# main.net
KiCad netlist of a schematic drawn in EAGLE
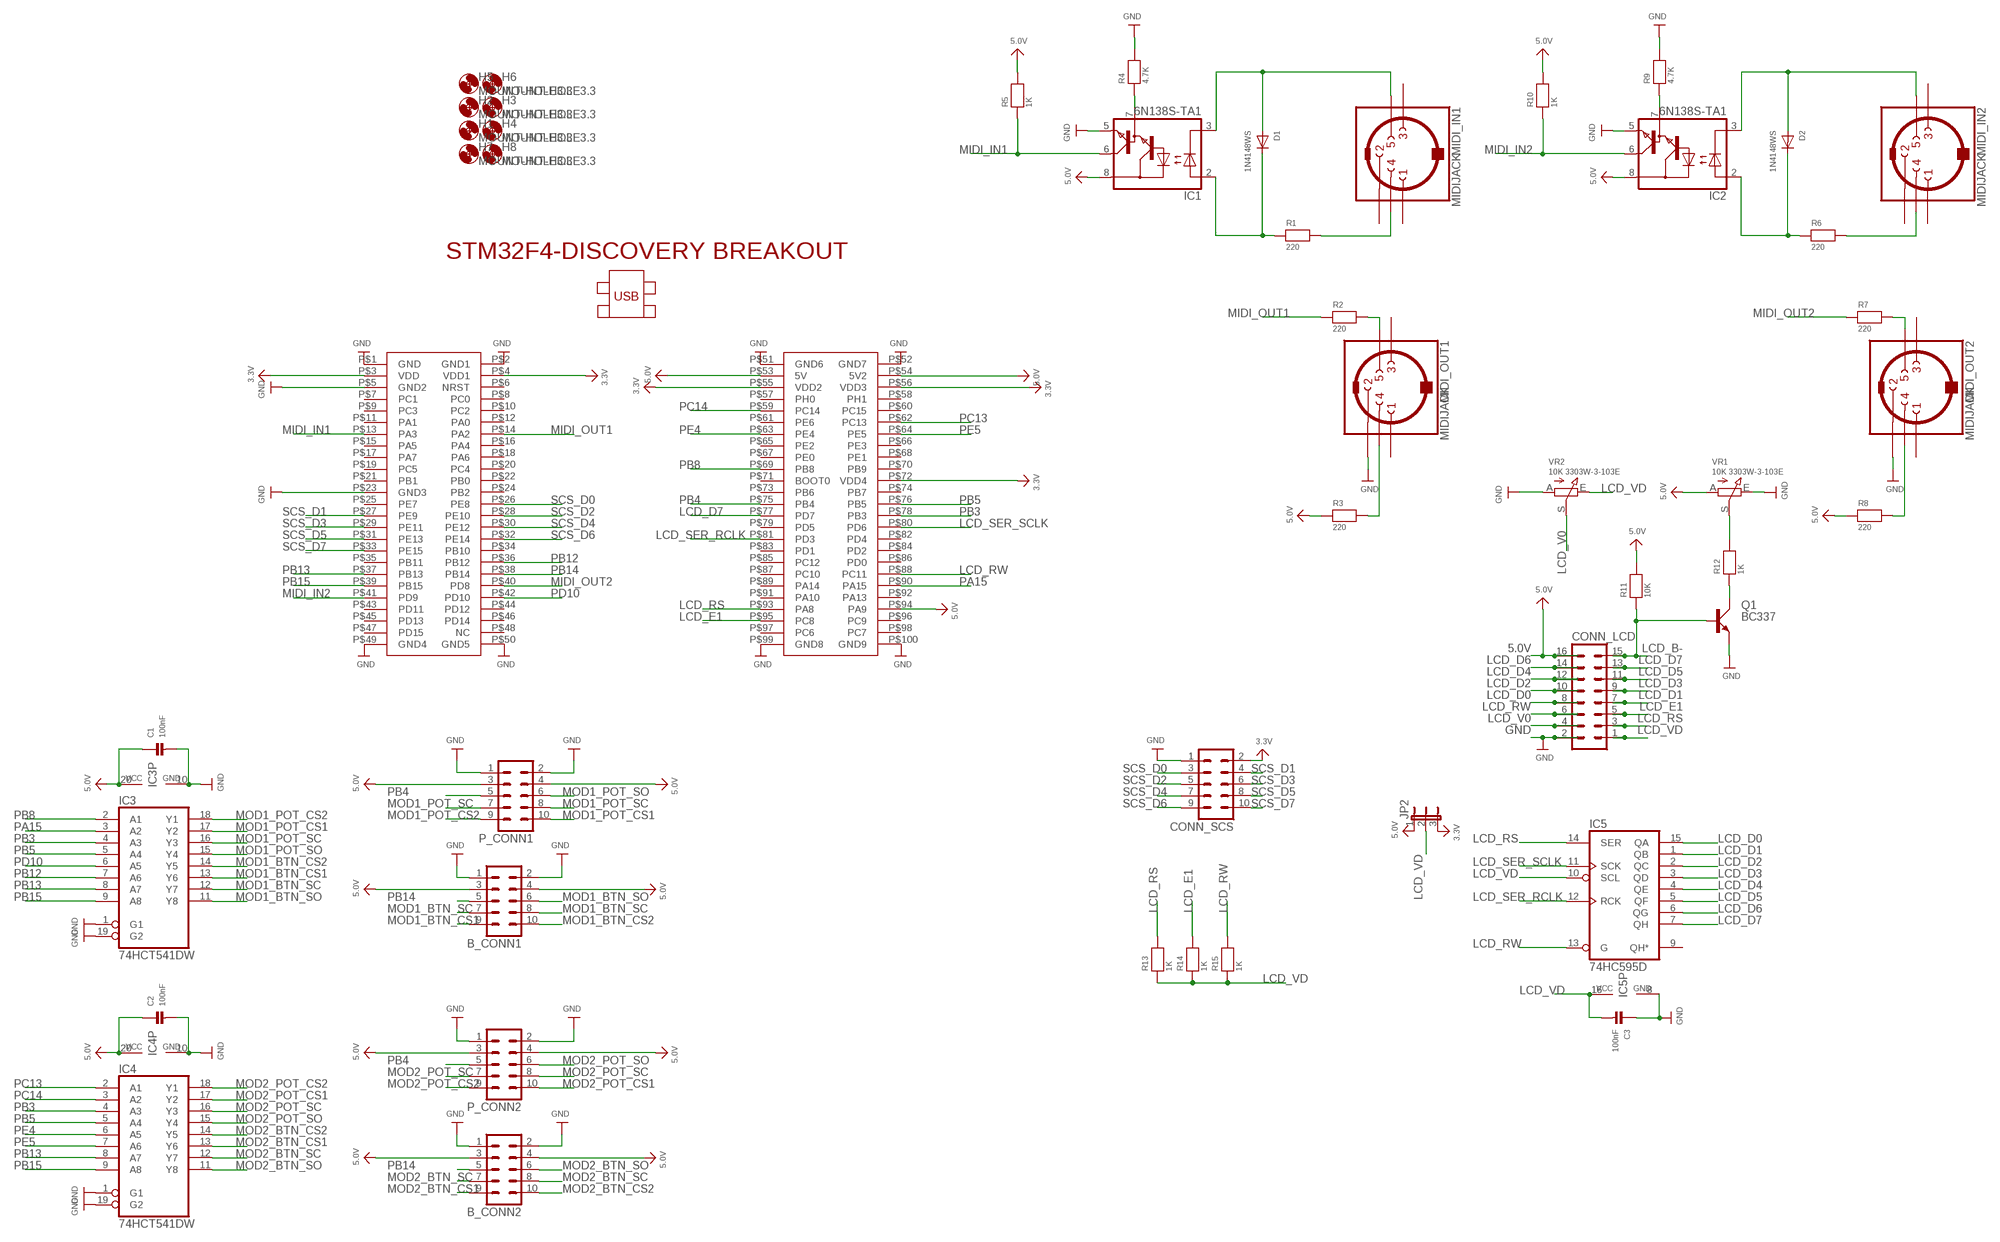
[diagram p0: schematic, sheet 1]

(export (version "E")
  (design (tool "Eeschema 10.0.6"))
  (components
    (comp (ref "B_CONN1")
      (value "ML10")
      (footprint "eagle-import:ML10")
      (libsource (lib "eagle-import") (part "ML10"))
    )
    (comp (ref "B_CONN2")
      (value "ML10")
      (footprint "eagle-import:ML10")
      (libsource (lib "eagle-import") (part "ML10"))
    )
    (comp (ref "C1")
      (value "100nF")
      (footprint "eagle-import:0603")
      (libsource (lib "eagle-import") (part "CAP_CERAMIC0603"))
    )
    (comp (ref "C2")
      (value "100nF")
      (footprint "eagle-import:0603")
      (libsource (lib "eagle-import") (part "CAP_CERAMIC0603"))
    )
    (comp (ref "C3")
      (value "100nF")
      (footprint "eagle-import:0603")
      (libsource (lib "eagle-import") (part "CAP_CERAMIC0603"))
    )
    (comp (ref "CONN_LCD")
      (value "ML16")
      (footprint "eagle-import:ML16")
      (libsource (lib "eagle-import") (part "ML16"))
    )
    (comp (ref "CONN_SCS")
      (value "ML10")
      (footprint "eagle-import:ML10")
      (libsource (lib "eagle-import") (part "ML10"))
    )
    (comp (ref "D1")
      (value "1N4148WS")
      (footprint "eagle-import:SOD-323")
      (libsource (lib "eagle-import") (part "DIODESOD-323"))
    )
    (comp (ref "D2")
      (value "1N4148WS")
      (footprint "eagle-import:SOD-323")
      (libsource (lib "eagle-import") (part "DIODESOD-323"))
    )
    (comp (ref "H1")
      (value "MOUNT-HOLE3.3")
      (footprint "eagle-import:3,3")
      (libsource (lib "eagle-import") (part "MOUNT-HOLE3.3"))
    )
    (comp (ref "H2")
      (value "MOUNT-HOLE3.3")
      (footprint "eagle-import:3,3")
      (libsource (lib "eagle-import") (part "MOUNT-HOLE3.3"))
    )
    (comp (ref "H3")
      (value "MOUNT-HOLE3.3")
      (footprint "eagle-import:3,3")
      (libsource (lib "eagle-import") (part "MOUNT-HOLE3.3"))
    )
    (comp (ref "H4")
      (value "MOUNT-HOLE3.3")
      (footprint "eagle-import:3,3")
      (libsource (lib "eagle-import") (part "MOUNT-HOLE3.3"))
    )
    (comp (ref "H5")
      (value "MOUNT-HOLE3.3")
      (footprint "eagle-import:3,3")
      (libsource (lib "eagle-import") (part "MOUNT-HOLE3.3"))
    )
    (comp (ref "H6")
      (value "MOUNT-HOLE3.3")
      (footprint "eagle-import:3,3")
      (libsource (lib "eagle-import") (part "MOUNT-HOLE3.3"))
    )
    (comp (ref "H7")
      (value "MOUNT-HOLE3.3")
      (footprint "eagle-import:3,3")
      (libsource (lib "eagle-import") (part "MOUNT-HOLE3.3"))
    )
    (comp (ref "H8")
      (value "MOUNT-HOLE3.3")
      (footprint "eagle-import:3,3")
      (libsource (lib "eagle-import") (part "MOUNT-HOLE3.3"))
    )
    (comp (ref "IC1")
      (value "6N138S-TA1")
      (footprint "eagle-import:SO8-GW300")
      (libsource (lib "eagle-import") (part "6N138SMD"))
    )
    (comp (ref "IC2")
      (value "6N138S-TA1")
      (footprint "eagle-import:SO8-GW300")
      (libsource (lib "eagle-import") (part "6N138SMD"))
    )
    (comp (ref "IC3")
      (value "74HCT541DW")
      (footprint "eagle-import:SO20W")
      (libsource (lib "eagle-import") (part "74541DWHCT"))
    )
    (comp (ref "IC4")
      (value "74HCT541DW")
      (footprint "eagle-import:SO20W")
      (libsource (lib "eagle-import") (part "74541DWHCT"))
    )
    (comp (ref "IC5")
      (value "74HC595D")
      (footprint "eagle-import:SO16")
      (libsource (lib "eagle-import") (part "74595DHC"))
    )
    (comp (ref "JP2")
      (value "JUMPER3")
      (footprint "eagle-import:JUMPER3")
      (libsource (lib "eagle-import") (part "JUMPER3"))
    )
    (comp (ref "MIDI_IN1")
      (value "MIDIJACK")
      (footprint "eagle-import:CP-2350")
      (libsource (lib "eagle-import") (part "MIDIJACK"))
    )
    (comp (ref "MIDI_IN2")
      (value "MIDIJACK")
      (footprint "eagle-import:CP-2350")
      (libsource (lib "eagle-import") (part "MIDIJACK"))
    )
    (comp (ref "MIDI_OUT1")
      (value "MIDIJACK")
      (footprint "eagle-import:CP-2350")
      (libsource (lib "eagle-import") (part "MIDIJACK"))
    )
    (comp (ref "MIDI_OUT2")
      (value "MIDIJACK")
      (footprint "eagle-import:CP-2350")
      (libsource (lib "eagle-import") (part "MIDIJACK"))
    )
    (comp (ref "P_CONN1")
      (value "ML10")
      (footprint "eagle-import:ML10")
      (libsource (lib "eagle-import") (part "ML10"))
    )
    (comp (ref "P_CONN2")
      (value "ML10")
      (footprint "eagle-import:ML10")
      (libsource (lib "eagle-import") (part "ML10"))
    )
    (comp (ref "Q1")
      (value "BC337")
      (footprint "eagle-import:SOT54A")
      (libsource (lib "eagle-import") (part "BC337"))
    )
    (comp (ref "R1")
      (value "220")
      (footprint "eagle-import:_0603")
      (libsource (lib "eagle-import") (part "RESISTOR_0603"))
    )
    (comp (ref "R2")
      (value "220")
      (footprint "eagle-import:_0603")
      (libsource (lib "eagle-import") (part "RESISTOR_0603"))
    )
    (comp (ref "R3")
      (value "220")
      (footprint "eagle-import:_0603")
      (libsource (lib "eagle-import") (part "RESISTOR_0603"))
    )
    (comp (ref "R4")
      (value "4.7K")
      (footprint "eagle-import:_0603")
      (libsource (lib "eagle-import") (part "RESISTOR_0603"))
    )
    (comp (ref "R5")
      (value "1K")
      (footprint "eagle-import:_0603")
      (libsource (lib "eagle-import") (part "RESISTOR_0603"))
    )
    (comp (ref "R6")
      (value "220")
      (footprint "eagle-import:_0603")
      (libsource (lib "eagle-import") (part "RESISTOR_0603"))
    )
    (comp (ref "R7")
      (value "220")
      (footprint "eagle-import:_0603")
      (libsource (lib "eagle-import") (part "RESISTOR_0603"))
    )
    (comp (ref "R8")
      (value "220")
      (footprint "eagle-import:_0603")
      (libsource (lib "eagle-import") (part "RESISTOR_0603"))
    )
    (comp (ref "R9")
      (value "4.7K")
      (footprint "eagle-import:_0603")
      (libsource (lib "eagle-import") (part "RESISTOR_0603"))
    )
    (comp (ref "R10")
      (value "1K")
      (footprint "eagle-import:_0603")
      (libsource (lib "eagle-import") (part "RESISTOR_0603"))
    )
    (comp (ref "R11")
      (value "10K")
      (footprint "eagle-import:_0603")
      (libsource (lib "eagle-import") (part "RESISTOR_0603"))
    )
    (comp (ref "R12")
      (value "1K")
      (footprint "eagle-import:_0603")
      (libsource (lib "eagle-import") (part "RESISTOR_0603"))
    )
    (comp (ref "R13")
      (value "1K")
      (footprint "eagle-import:_0603")
      (libsource (lib "eagle-import") (part "RESISTOR_0603"))
    )
    (comp (ref "R14")
      (value "1K")
      (footprint "eagle-import:_0603")
      (libsource (lib "eagle-import") (part "RESISTOR_0603"))
    )
    (comp (ref "R15")
      (value "1K")
      (footprint "eagle-import:_0603")
      (libsource (lib "eagle-import") (part "RESISTOR_0603"))
    )
    (comp (ref "U$1")
      (value "STM32F4-DISCOVERY")
      (footprint "eagle-import:STM32F4-DISCOVERY")
      (libsource (lib "eagle-import") (part "STM32F4-DISCOVERY"))
    )
    (comp (ref "VR1")
      (value "10K 3303W-3-103E")
      (footprint "eagle-import:TRIMPOT_BOURNS3MM")
      (libsource (lib "eagle-import") (part "TRIMPOT10K_BOURNS"))
    )
    (comp (ref "VR2")
      (value "10K 3303W-3-103E")
      (footprint "eagle-import:TRIMPOT_BOURNS3MM")
      (libsource (lib "eagle-import") (part "TRIMPOT10K_BOURNS"))
    )
  )
  (nets
    (net (code "1") (name "/LCD_B-") (class "Default")
      (node (ref "CONN_LCD") (pin "15") (pinfunction "15_15") (pintype "passive"))
      (node (ref "Q1") (pin "B") (pinfunction "B_B") (pintype "passive"))
      (node (ref "R11") (pin "1") (pinfunction "1_1") (pintype "passive"))
    )
    (net (code "2") (name "/LCD_D0") (class "Default")
      (node (ref "CONN_LCD") (pin "8") (pinfunction "8_8") (pintype "passive"))
      (node (ref "IC5") (pin "15") (pinfunction "QA_15") (pintype "tri_state"))
    )
    (net (code "3") (name "/LCD_D1") (class "Default")
      (node (ref "CONN_LCD") (pin "7") (pinfunction "7_7") (pintype "passive"))
      (node (ref "IC5") (pin "1") (pinfunction "QB_1") (pintype "tri_state"))
    )
    (net (code "4") (name "/LCD_D2") (class "Default")
      (node (ref "CONN_LCD") (pin "10") (pinfunction "10_10") (pintype "passive"))
      (node (ref "IC5") (pin "2") (pinfunction "QC_2") (pintype "tri_state"))
    )
    (net (code "5") (name "/LCD_D3") (class "Default")
      (node (ref "CONN_LCD") (pin "9") (pinfunction "9_9") (pintype "passive"))
      (node (ref "IC5") (pin "3") (pinfunction "QD_3") (pintype "tri_state"))
    )
    (net (code "6") (name "/LCD_D4") (class "Default")
      (node (ref "CONN_LCD") (pin "12") (pinfunction "12_12") (pintype "passive"))
      (node (ref "IC5") (pin "4") (pinfunction "QE_4") (pintype "tri_state"))
    )
    (net (code "7") (name "/LCD_D5") (class "Default")
      (node (ref "CONN_LCD") (pin "11") (pinfunction "11_11") (pintype "passive"))
      (node (ref "IC5") (pin "5") (pinfunction "QF_5") (pintype "tri_state"))
    )
    (net (code "8") (name "/LCD_D6") (class "Default")
      (node (ref "CONN_LCD") (pin "14") (pinfunction "14_14") (pintype "passive"))
      (node (ref "IC5") (pin "6") (pinfunction "QG_6") (pintype "tri_state"))
    )
    (net (code "9") (name "/LCD_D7") (class "Default")
      (node (ref "CONN_LCD") (pin "13") (pinfunction "13_13") (pintype "passive"))
      (node (ref "IC5") (pin "7") (pinfunction "QH_7") (pintype "tri_state"))
      (node (ref "U$1") (pin "P$77") (pinfunction "PD7_P$77") (pintype "bidirectional"))
    )
    (net (code "10") (name "/LCD_E1") (class "Default")
      (node (ref "CONN_LCD") (pin "5") (pinfunction "5_5") (pintype "passive"))
      (node (ref "R14") (pin "2") (pinfunction "2_2") (pintype "passive"))
      (node (ref "U$1") (pin "P$95") (pinfunction "PC8_P$95") (pintype "bidirectional"))
    )
    (net (code "11") (name "/LCD_RS") (class "Default")
      (node (ref "CONN_LCD") (pin "3") (pinfunction "3_3") (pintype "passive"))
      (node (ref "IC5") (pin "14") (pinfunction "SER_14") (pintype "input"))
      (node (ref "R13") (pin "2") (pinfunction "2_2") (pintype "passive"))
      (node (ref "U$1") (pin "P$93") (pinfunction "PA8_P$93") (pintype "bidirectional"))
    )
    (net (code "12") (name "/LCD_RW") (class "Default")
      (node (ref "CONN_LCD") (pin "6") (pinfunction "6_6") (pintype "passive"))
      (node (ref "IC5") (pin "13") (pinfunction "G_13") (pintype "input"))
      (node (ref "R15") (pin "2") (pinfunction "2_2") (pintype "passive"))
      (node (ref "U$1") (pin "P$88") (pinfunction "PC11_P$88") (pintype "bidirectional"))
    )
    (net (code "13") (name "/LCD_SER_RCLK") (class "Default")
      (node (ref "IC5") (pin "12") (pinfunction "RCK_12") (pintype "input"))
      (node (ref "U$1") (pin "P$81") (pinfunction "PD3_P$81") (pintype "bidirectional"))
    )
    (net (code "14") (name "/LCD_SER_SCLK") (class "Default")
      (node (ref "IC5") (pin "11") (pinfunction "SCK_11") (pintype "input"))
      (node (ref "U$1") (pin "P$80") (pinfunction "PD6_P$80") (pintype "bidirectional"))
    )
    (net (code "15") (name "/LCD_V0") (class "Default")
      (node (ref "CONN_LCD") (pin "4") (pinfunction "4_4") (pintype "passive"))
      (node (ref "VR2") (pin "S") (pinfunction "S_S") (pintype "passive"))
    )
    (net (code "16") (name "/LCD_VD") (class "Default")
      (node (ref "C3") (pin "2") (pinfunction "P$2_2") (pintype "passive"))
      (node (ref "CONN_LCD") (pin "1") (pinfunction "1_1") (pintype "passive"))
      (node (ref "IC5") (pin "10") (pinfunction "SCL_10") (pintype "input"))
      (node (ref "IC5") (pin "16") (pinfunction "VCC_16") (pintype "power_in"))
      (node (ref "JP2") (pin "2") (pinfunction "2_2") (pintype "passive"))
      (node (ref "R13") (pin "1") (pinfunction "1_1") (pintype "passive"))
      (node (ref "R14") (pin "1") (pinfunction "1_1") (pintype "passive"))
      (node (ref "R15") (pin "1") (pinfunction "1_1") (pintype "passive"))
      (node (ref "VR2") (pin "E") (pinfunction "E_E") (pintype "passive"))
    )
    (net (code "17") (name "/MIDI_IN1") (class "Default")
      (node (ref "IC1") (pin "6") (pinfunction "VO_6") (pintype "passive"))
      (node (ref "R5") (pin "1") (pinfunction "1_1") (pintype "passive"))
      (node (ref "U$1") (pin "P$13") (pinfunction "PA3_P$13") (pintype "bidirectional"))
    )
    (net (code "18") (name "/MIDI_IN2") (class "Default")
      (node (ref "IC2") (pin "6") (pinfunction "VO_6") (pintype "passive"))
      (node (ref "R10") (pin "1") (pinfunction "1_1") (pintype "passive"))
      (node (ref "U$1") (pin "P$41") (pinfunction "PD9_P$41") (pintype "bidirectional"))
    )
    (net (code "19") (name "/MIDI_OUT1") (class "Default")
      (node (ref "R2") (pin "1") (pinfunction "1_1") (pintype "passive"))
      (node (ref "U$1") (pin "P$14") (pinfunction "PA2_P$14") (pintype "bidirectional"))
    )
    (net (code "20") (name "/MIDI_OUT2") (class "Default")
      (node (ref "R7") (pin "1") (pinfunction "1_1") (pintype "passive"))
      (node (ref "U$1") (pin "P$40") (pinfunction "PD8_P$40") (pintype "bidirectional"))
    )
    (net (code "21") (name "/MOD1_BTN_CS1") (class "Default")
      (node (ref "B_CONN1") (pin "9") (pinfunction "9_9") (pintype "passive"))
      (node (ref "IC3") (pin "13") (pinfunction "Y6_13") (pintype "tri_state"))
    )
    (net (code "22") (name "/MOD1_BTN_CS2") (class "Default")
      (node (ref "B_CONN1") (pin "10") (pinfunction "10_10") (pintype "passive"))
      (node (ref "IC3") (pin "14") (pinfunction "Y5_14") (pintype "tri_state"))
    )
    (net (code "23") (name "/MOD1_BTN_SC") (class "Default")
      (node (ref "B_CONN1") (pin "7") (pinfunction "7_7") (pintype "passive"))
      (node (ref "B_CONN1") (pin "8") (pinfunction "8_8") (pintype "passive"))
      (node (ref "IC3") (pin "12") (pinfunction "Y7_12") (pintype "tri_state"))
    )
    (net (code "24") (name "/MOD1_BTN_SO") (class "Default")
      (node (ref "B_CONN1") (pin "6") (pinfunction "6_6") (pintype "passive"))
      (node (ref "IC3") (pin "11") (pinfunction "Y8_11") (pintype "tri_state"))
    )
    (net (code "25") (name "/MOD1_POT_CS1") (class "Default")
      (node (ref "IC3") (pin "17") (pinfunction "Y2_17") (pintype "tri_state"))
      (node (ref "P_CONN1") (pin "10") (pinfunction "10_10") (pintype "passive"))
    )
    (net (code "26") (name "/MOD1_POT_CS2") (class "Default")
      (node (ref "IC3") (pin "18") (pinfunction "Y1_18") (pintype "tri_state"))
      (node (ref "P_CONN1") (pin "9") (pinfunction "9_9") (pintype "passive"))
    )
    (net (code "27") (name "/MOD1_POT_SC") (class "Default")
      (node (ref "IC3") (pin "16") (pinfunction "Y3_16") (pintype "tri_state"))
      (node (ref "P_CONN1") (pin "7") (pinfunction "7_7") (pintype "passive"))
      (node (ref "P_CONN1") (pin "8") (pinfunction "8_8") (pintype "passive"))
    )
    (net (code "28") (name "/MOD1_POT_SO") (class "Default")
      (node (ref "IC3") (pin "15") (pinfunction "Y4_15") (pintype "tri_state"))
      (node (ref "P_CONN1") (pin "6") (pinfunction "6_6") (pintype "passive"))
    )
    (net (code "29") (name "/MOD2_BTN_CS1") (class "Default")
      (node (ref "B_CONN2") (pin "9") (pinfunction "9_9") (pintype "passive"))
      (node (ref "IC4") (pin "13") (pinfunction "Y6_13") (pintype "tri_state"))
    )
    (net (code "30") (name "/MOD2_BTN_CS2") (class "Default")
      (node (ref "B_CONN2") (pin "10") (pinfunction "10_10") (pintype "passive"))
      (node (ref "IC4") (pin "14") (pinfunction "Y5_14") (pintype "tri_state"))
    )
    (net (code "31") (name "/MOD2_BTN_SC") (class "Default")
      (node (ref "B_CONN2") (pin "7") (pinfunction "7_7") (pintype "passive"))
      (node (ref "B_CONN2") (pin "8") (pinfunction "8_8") (pintype "passive"))
      (node (ref "IC4") (pin "12") (pinfunction "Y7_12") (pintype "tri_state"))
    )
    (net (code "32") (name "/MOD2_BTN_SO") (class "Default")
      (node (ref "B_CONN2") (pin "6") (pinfunction "6_6") (pintype "passive"))
      (node (ref "IC4") (pin "11") (pinfunction "Y8_11") (pintype "tri_state"))
    )
    (net (code "33") (name "/MOD2_POT_CS1") (class "Default")
      (node (ref "IC4") (pin "17") (pinfunction "Y2_17") (pintype "tri_state"))
      (node (ref "P_CONN2") (pin "10") (pinfunction "10_10") (pintype "passive"))
    )
    (net (code "34") (name "/MOD2_POT_CS2") (class "Default")
      (node (ref "IC4") (pin "18") (pinfunction "Y1_18") (pintype "tri_state"))
      (node (ref "P_CONN2") (pin "9") (pinfunction "9_9") (pintype "passive"))
    )
    (net (code "35") (name "/MOD2_POT_SC") (class "Default")
      (node (ref "IC4") (pin "16") (pinfunction "Y3_16") (pintype "tri_state"))
      (node (ref "P_CONN2") (pin "7") (pinfunction "7_7") (pintype "passive"))
      (node (ref "P_CONN2") (pin "8") (pinfunction "8_8") (pintype "passive"))
    )
    (net (code "36") (name "/MOD2_POT_SO") (class "Default")
      (node (ref "IC4") (pin "15") (pinfunction "Y4_15") (pintype "tri_state"))
      (node (ref "P_CONN2") (pin "6") (pinfunction "6_6") (pintype "passive"))
    )
    (net (code "37") (name "/PA15") (class "Default")
      (node (ref "IC3") (pin "3") (pinfunction "A2_3") (pintype "input"))
      (node (ref "U$1") (pin "P$90") (pinfunction "PA15_P$90") (pintype "bidirectional"))
    )
    (net (code "38") (name "/PB3") (class "Default")
      (node (ref "IC3") (pin "4") (pinfunction "A3_4") (pintype "input"))
      (node (ref "IC4") (pin "4") (pinfunction "A3_4") (pintype "input"))
      (node (ref "U$1") (pin "P$78") (pinfunction "PB3_P$78") (pintype "bidirectional"))
    )
    (net (code "39") (name "/PB4") (class "Default")
      (node (ref "P_CONN1") (pin "5") (pinfunction "5_5") (pintype "passive"))
      (node (ref "P_CONN2") (pin "5") (pinfunction "5_5") (pintype "passive"))
      (node (ref "U$1") (pin "P$75") (pinfunction "PB4_P$75") (pintype "bidirectional"))
    )
    (net (code "40") (name "/PB5") (class "Default")
      (node (ref "IC3") (pin "5") (pinfunction "A4_5") (pintype "input"))
      (node (ref "IC4") (pin "5") (pinfunction "A4_5") (pintype "input"))
      (node (ref "U$1") (pin "P$76") (pinfunction "PB5_P$76") (pintype "bidirectional"))
    )
    (net (code "41") (name "/PB8") (class "Default")
      (node (ref "IC3") (pin "2") (pinfunction "A1_2") (pintype "input"))
      (node (ref "U$1") (pin "P$69") (pinfunction "PB8_P$69") (pintype "bidirectional"))
    )
    (net (code "42") (name "/PB12") (class "Default")
      (node (ref "IC3") (pin "7") (pinfunction "A6_7") (pintype "input"))
      (node (ref "U$1") (pin "P$36") (pinfunction "PB12_P$36") (pintype "bidirectional"))
    )
    (net (code "43") (name "/PB13") (class "Default")
      (node (ref "IC3") (pin "8") (pinfunction "A7_8") (pintype "input"))
      (node (ref "IC4") (pin "8") (pinfunction "A7_8") (pintype "input"))
      (node (ref "U$1") (pin "P$37") (pinfunction "PB13_P$37") (pintype "bidirectional"))
    )
    (net (code "44") (name "/PB14") (class "Default")
      (node (ref "B_CONN1") (pin "5") (pinfunction "5_5") (pintype "passive"))
      (node (ref "B_CONN2") (pin "5") (pinfunction "5_5") (pintype "passive"))
      (node (ref "U$1") (pin "P$38") (pinfunction "PB14_P$38") (pintype "bidirectional"))
    )
    (net (code "45") (name "/PB15") (class "Default")
      (node (ref "IC3") (pin "9") (pinfunction "A8_9") (pintype "input"))
      (node (ref "IC4") (pin "9") (pinfunction "A8_9") (pintype "input"))
      (node (ref "U$1") (pin "P$39") (pinfunction "PB15_P$39") (pintype "bidirectional"))
    )
    (net (code "46") (name "/PC13") (class "Default")
      (node (ref "IC4") (pin "2") (pinfunction "A1_2") (pintype "input"))
      (node (ref "U$1") (pin "P$62") (pinfunction "PC13_P$62") (pintype "bidirectional"))
    )
    (net (code "47") (name "/PC14") (class "Default")
      (node (ref "IC4") (pin "3") (pinfunction "A2_3") (pintype "input"))
      (node (ref "U$1") (pin "P$59") (pinfunction "PC14_P$59") (pintype "bidirectional"))
    )
    (net (code "48") (name "/PD10") (class "Default")
      (node (ref "IC3") (pin "6") (pinfunction "A5_6") (pintype "input"))
      (node (ref "U$1") (pin "P$42") (pinfunction "PD10_P$42") (pintype "bidirectional"))
    )
    (net (code "49") (name "/PE4") (class "Default")
      (node (ref "IC4") (pin "6") (pinfunction "A5_6") (pintype "input"))
      (node (ref "U$1") (pin "P$63") (pinfunction "PE4_P$63") (pintype "bidirectional"))
    )
    (net (code "50") (name "/PE5") (class "Default")
      (node (ref "IC4") (pin "7") (pinfunction "A6_7") (pintype "input"))
      (node (ref "U$1") (pin "P$64") (pinfunction "PE5_P$64") (pintype "bidirectional"))
    )
    (net (code "51") (name "/SCS_D0") (class "Default")
      (node (ref "CONN_SCS") (pin "3") (pinfunction "3_3") (pintype "passive"))
      (node (ref "U$1") (pin "P$26") (pinfunction "PE8_P$26") (pintype "bidirectional"))
    )
    (net (code "52") (name "/SCS_D1") (class "Default")
      (node (ref "CONN_SCS") (pin "4") (pinfunction "4_4") (pintype "passive"))
      (node (ref "U$1") (pin "P$27") (pinfunction "PE9_P$27") (pintype "bidirectional"))
    )
    (net (code "53") (name "/SCS_D2") (class "Default")
      (node (ref "CONN_SCS") (pin "5") (pinfunction "5_5") (pintype "passive"))
      (node (ref "U$1") (pin "P$28") (pinfunction "PE10_P$28") (pintype "bidirectional"))
    )
    (net (code "54") (name "/SCS_D3") (class "Default")
      (node (ref "CONN_SCS") (pin "6") (pinfunction "6_6") (pintype "passive"))
      (node (ref "U$1") (pin "P$29") (pinfunction "PE11_P$29") (pintype "bidirectional"))
    )
    (net (code "55") (name "/SCS_D4") (class "Default")
      (node (ref "CONN_SCS") (pin "7") (pinfunction "7_7") (pintype "passive"))
      (node (ref "U$1") (pin "P$30") (pinfunction "PE12_P$30") (pintype "bidirectional"))
    )
    (net (code "56") (name "/SCS_D5") (class "Default")
      (node (ref "CONN_SCS") (pin "8") (pinfunction "8_8") (pintype "passive"))
      (node (ref "U$1") (pin "P$31") (pinfunction "PE13_P$31") (pintype "bidirectional"))
    )
    (net (code "57") (name "/SCS_D6") (class "Default")
      (node (ref "CONN_SCS") (pin "9") (pinfunction "9_9") (pintype "passive"))
      (node (ref "U$1") (pin "P$32") (pinfunction "PE14_P$32") (pintype "bidirectional"))
    )
    (net (code "58") (name "/SCS_D7") (class "Default")
      (node (ref "CONN_SCS") (pin "10") (pinfunction "10_10") (pintype "passive"))
      (node (ref "U$1") (pin "P$33") (pinfunction "PE15_P$33") (pintype "bidirectional"))
    )
    (net (code "59") (name "3.3V") (class "Default")
      (node (ref "CONN_SCS") (pin "2") (pinfunction "2_2") (pintype "passive"))
      (node (ref "JP2") (pin "3") (pinfunction "3_3") (pintype "passive"))
      (node (ref "U$1") (pin "P$3") (pinfunction "VDD_P$3") (pintype "bidirectional"))
      (node (ref "U$1") (pin "P$4") (pinfunction "VDD1_P$4") (pintype "bidirectional"))
      (node (ref "U$1") (pin "P$55") (pinfunction "VDD2_P$55") (pintype "bidirectional"))
      (node (ref "U$1") (pin "P$56") (pinfunction "VDD3_P$56") (pintype "bidirectional"))
      (node (ref "U$1") (pin "P$72") (pinfunction "VDD4_P$72") (pintype "bidirectional"))
    )
    (net (code "60") (name "5.0V") (class "Default")
      (node (ref "B_CONN1") (pin "3") (pinfunction "3_3") (pintype "passive"))
      (node (ref "B_CONN1") (pin "4") (pinfunction "4_4") (pintype "passive"))
      (node (ref "B_CONN2") (pin "3") (pinfunction "3_3") (pintype "passive"))
      (node (ref "B_CONN2") (pin "4") (pinfunction "4_4") (pintype "passive"))
      (node (ref "C1") (pin "1") (pinfunction "P$1_1") (pintype "passive"))
      (node (ref "C2") (pin "1") (pinfunction "P$1_1") (pintype "passive"))
      (node (ref "CONN_LCD") (pin "16") (pinfunction "16_16") (pintype "passive"))
      (node (ref "IC1") (pin "8") (pinfunction "VCC_8") (pintype "passive"))
      (node (ref "IC2") (pin "8") (pinfunction "VCC_8") (pintype "passive"))
      (node (ref "IC3") (pin "20") (pinfunction "VCC_20") (pintype "power_in"))
      (node (ref "IC4") (pin "20") (pinfunction "VCC_20") (pintype "power_in"))
      (node (ref "JP2") (pin "1") (pinfunction "1_1") (pintype "passive"))
      (node (ref "P_CONN1") (pin "3") (pinfunction "3_3") (pintype "passive"))
      (node (ref "P_CONN1") (pin "4") (pinfunction "4_4") (pintype "passive"))
      (node (ref "P_CONN2") (pin "3") (pinfunction "3_3") (pintype "passive"))
      (node (ref "P_CONN2") (pin "4") (pinfunction "4_4") (pintype "passive"))
      (node (ref "R10") (pin "2") (pinfunction "2_2") (pintype "passive"))
      (node (ref "R11") (pin "2") (pinfunction "2_2") (pintype "passive"))
      (node (ref "R3") (pin "1") (pinfunction "1_1") (pintype "passive"))
      (node (ref "R5") (pin "2") (pinfunction "2_2") (pintype "passive"))
      (node (ref "R8") (pin "1") (pinfunction "1_1") (pintype "passive"))
      (node (ref "U$1") (pin "P$53") (pinfunction "5V_P$53") (pintype "bidirectional"))
      (node (ref "U$1") (pin "P$54") (pinfunction "5V2_P$54") (pintype "bidirectional"))
      (node (ref "U$1") (pin "P$94") (pinfunction "PA9_P$94") (pintype "bidirectional"))
      (node (ref "VR1") (pin "A") (pinfunction "A_A") (pintype "passive"))
    )
    (net (code "61") (name "GND") (class "Default")
      (node (ref "B_CONN1") (pin "1") (pinfunction "1_1") (pintype "passive"))
      (node (ref "B_CONN1") (pin "2") (pinfunction "2_2") (pintype "passive"))
      (node (ref "B_CONN2") (pin "1") (pinfunction "1_1") (pintype "passive"))
      (node (ref "B_CONN2") (pin "2") (pinfunction "2_2") (pintype "passive"))
      (node (ref "C1") (pin "2") (pinfunction "P$2_2") (pintype "passive"))
      (node (ref "C2") (pin "2") (pinfunction "P$2_2") (pintype "passive"))
      (node (ref "C3") (pin "1") (pinfunction "P$1_1") (pintype "passive"))
      (node (ref "CONN_LCD") (pin "2") (pinfunction "2_2") (pintype "passive"))
      (node (ref "CONN_SCS") (pin "1") (pinfunction "1_1") (pintype "passive"))
      (node (ref "IC1") (pin "5") (pinfunction "GND_5") (pintype "passive"))
      (node (ref "IC2") (pin "5") (pinfunction "GND_5") (pintype "passive"))
      (node (ref "IC3") (pin "1") (pinfunction "G1_1") (pintype "input"))
      (node (ref "IC3") (pin "10") (pinfunction "GND_10") (pintype "power_in"))
      (node (ref "IC3") (pin "19") (pinfunction "G2_19") (pintype "input"))
      (node (ref "IC4") (pin "1") (pinfunction "G1_1") (pintype "input"))
      (node (ref "IC4") (pin "10") (pinfunction "GND_10") (pintype "power_in"))
      (node (ref "IC4") (pin "19") (pinfunction "G2_19") (pintype "input"))
      (node (ref "IC5") (pin "8") (pinfunction "GND_8") (pintype "power_in"))
      (node (ref "MIDI_OUT1") (pin "2") (pinfunction "2_2") (pintype "passive"))
      (node (ref "MIDI_OUT2") (pin "2") (pinfunction "2_2") (pintype "passive"))
      (node (ref "P_CONN1") (pin "1") (pinfunction "1_1") (pintype "passive"))
      (node (ref "P_CONN1") (pin "2") (pinfunction "2_2") (pintype "passive"))
      (node (ref "P_CONN2") (pin "1") (pinfunction "1_1") (pintype "passive"))
      (node (ref "P_CONN2") (pin "2") (pinfunction "2_2") (pintype "passive"))
      (node (ref "Q1") (pin "E") (pinfunction "E_E") (pintype "passive"))
      (node (ref "R4") (pin "2") (pinfunction "2_2") (pintype "passive"))
      (node (ref "R9") (pin "2") (pinfunction "2_2") (pintype "passive"))
      (node (ref "U$1") (pin "P$1") (pinfunction "GND_P$1") (pintype "bidirectional"))
      (node (ref "U$1") (pin "P$100") (pinfunction "GND9_P$100") (pintype "bidirectional"))
      (node (ref "U$1") (pin "P$2") (pinfunction "GND1_P$2") (pintype "bidirectional"))
      (node (ref "U$1") (pin "P$23") (pinfunction "GND3_P$23") (pintype "bidirectional"))
      (node (ref "U$1") (pin "P$49") (pinfunction "GND4_P$49") (pintype "bidirectional"))
      (node (ref "U$1") (pin "P$5") (pinfunction "GND2_P$5") (pintype "bidirectional"))
      (node (ref "U$1") (pin "P$50") (pinfunction "GND5_P$50") (pintype "bidirectional"))
      (node (ref "U$1") (pin "P$51") (pinfunction "GND6_P$51") (pintype "bidirectional"))
      (node (ref "U$1") (pin "P$52") (pinfunction "GND7_P$52") (pintype "bidirectional"))
      (node (ref "U$1") (pin "P$99") (pinfunction "GND8_P$99") (pintype "bidirectional"))
      (node (ref "VR1") (pin "E") (pinfunction "E_E") (pintype "passive"))
      (node (ref "VR2") (pin "A") (pinfunction "A_A") (pintype "passive"))
    )
    (net (code "62") (name "Net-(IC1-A)") (class "Default")
      (node (ref "D1") (pin "C") (pinfunction "C_C") (pintype "passive"))
      (node (ref "IC1") (pin "2") (pinfunction "A_2") (pintype "passive"))
      (node (ref "R1") (pin "1") (pinfunction "1_1") (pintype "passive"))
    )
    (net (code "63") (name "Net-(IC1-C)") (class "Default")
      (node (ref "D1") (pin "A") (pinfunction "A_A") (pintype "passive"))
      (node (ref "IC1") (pin "3") (pinfunction "C_3") (pintype "passive"))
      (node (ref "MIDI_IN1") (pin "5") (pinfunction "5_5") (pintype "passive"))
    )
    (net (code "64") (name "Net-(IC1-VB)") (class "Default")
      (node (ref "IC1") (pin "7") (pinfunction "VB_7") (pintype "passive"))
      (node (ref "R4") (pin "1") (pinfunction "1_1") (pintype "passive"))
    )
    (net (code "65") (name "Net-(IC2-A)") (class "Default")
      (node (ref "D2") (pin "C") (pinfunction "C_C") (pintype "passive"))
      (node (ref "IC2") (pin "2") (pinfunction "A_2") (pintype "passive"))
      (node (ref "R6") (pin "1") (pinfunction "1_1") (pintype "passive"))
    )
    (net (code "66") (name "Net-(IC2-C)") (class "Default")
      (node (ref "D2") (pin "A") (pinfunction "A_A") (pintype "passive"))
      (node (ref "IC2") (pin "3") (pinfunction "C_3") (pintype "passive"))
      (node (ref "MIDI_IN2") (pin "5") (pinfunction "5_5") (pintype "passive"))
    )
    (net (code "67") (name "Net-(IC2-VB)") (class "Default")
      (node (ref "IC2") (pin "7") (pinfunction "VB_7") (pintype "passive"))
      (node (ref "R9") (pin "1") (pinfunction "1_1") (pintype "passive"))
    )
    (net (code "68") (name "Net-(MIDI_IN1-Pad4)") (class "Default")
      (node (ref "MIDI_IN1") (pin "4") (pinfunction "4_4") (pintype "passive"))
      (node (ref "R1") (pin "2") (pinfunction "2_2") (pintype "passive"))
    )
    (net (code "69") (name "Net-(MIDI_IN2-Pad4)") (class "Default")
      (node (ref "MIDI_IN2") (pin "4") (pinfunction "4_4") (pintype "passive"))
      (node (ref "R6") (pin "2") (pinfunction "2_2") (pintype "passive"))
    )
    (net (code "70") (name "Net-(MIDI_OUT1-Pad4)") (class "Default")
      (node (ref "MIDI_OUT1") (pin "4") (pinfunction "4_4") (pintype "passive"))
      (node (ref "R3") (pin "2") (pinfunction "2_2") (pintype "passive"))
    )
    (net (code "71") (name "Net-(MIDI_OUT1-Pad5)") (class "Default")
      (node (ref "MIDI_OUT1") (pin "5") (pinfunction "5_5") (pintype "passive"))
      (node (ref "R2") (pin "2") (pinfunction "2_2") (pintype "passive"))
    )
    (net (code "72") (name "Net-(MIDI_OUT2-Pad4)") (class "Default")
      (node (ref "MIDI_OUT2") (pin "4") (pinfunction "4_4") (pintype "passive"))
      (node (ref "R8") (pin "2") (pinfunction "2_2") (pintype "passive"))
    )
    (net (code "73") (name "Net-(MIDI_OUT2-Pad5)") (class "Default")
      (node (ref "MIDI_OUT2") (pin "5") (pinfunction "5_5") (pintype "passive"))
      (node (ref "R7") (pin "2") (pinfunction "2_2") (pintype "passive"))
    )
    (net (code "74") (name "Net-(Q1-PadC)") (class "Default")
      (node (ref "Q1") (pin "C") (pinfunction "C_C") (pintype "passive"))
      (node (ref "R12") (pin "1") (pinfunction "1_1") (pintype "passive"))
    )
    (net (code "75") (name "Net-(R12-Pad2)") (class "Default")
      (node (ref "R12") (pin "2") (pinfunction "2_2") (pintype "passive"))
      (node (ref "VR1") (pin "S") (pinfunction "S_S") (pintype "passive"))
    )
    (net (code "76") (name "unconnected-(IC5A-QH*-Pad9)") (class "Default")
      (node (ref "IC5") (pin "9") (pinfunction "QH*_9") (pintype "tri_state"))
    )
    (net (code "77") (name "unconnected-(MIDI_IN1-Pad1)") (class "Default")
      (node (ref "MIDI_IN1") (pin "1") (pinfunction "1_1") (pintype "passive"))
    )
    (net (code "78") (name "unconnected-(MIDI_IN1-Pad2)") (class "Default")
      (node (ref "MIDI_IN1") (pin "2") (pinfunction "2_2") (pintype "passive"))
    )
    (net (code "79") (name "unconnected-(MIDI_IN1-Pad3)") (class "Default")
      (node (ref "MIDI_IN1") (pin "3") (pinfunction "3_3") (pintype "passive"))
    )
    (net (code "80") (name "unconnected-(MIDI_IN2-Pad1)") (class "Default")
      (node (ref "MIDI_IN2") (pin "1") (pinfunction "1_1") (pintype "passive"))
    )
    (net (code "81") (name "unconnected-(MIDI_IN2-Pad2)") (class "Default")
      (node (ref "MIDI_IN2") (pin "2") (pinfunction "2_2") (pintype "passive"))
    )
    (net (code "82") (name "unconnected-(MIDI_IN2-Pad3)") (class "Default")
      (node (ref "MIDI_IN2") (pin "3") (pinfunction "3_3") (pintype "passive"))
    )
    (net (code "83") (name "unconnected-(MIDI_OUT1-Pad1)") (class "Default")
      (node (ref "MIDI_OUT1") (pin "1") (pinfunction "1_1") (pintype "passive"))
    )
    (net (code "84") (name "unconnected-(MIDI_OUT1-Pad3)") (class "Default")
      (node (ref "MIDI_OUT1") (pin "3") (pinfunction "3_3") (pintype "passive"))
    )
    (net (code "85") (name "unconnected-(MIDI_OUT2-Pad1)") (class "Default")
      (node (ref "MIDI_OUT2") (pin "1") (pinfunction "1_1") (pintype "passive"))
    )
    (net (code "86") (name "unconnected-(MIDI_OUT2-Pad3)") (class "Default")
      (node (ref "MIDI_OUT2") (pin "3") (pinfunction "3_3") (pintype "passive"))
    )
    (net (code "87") (name "unconnected-(U$1-BOOT0-PadP$71)") (class "Default")
      (node (ref "U$1") (pin "P$71") (pinfunction "BOOT0_P$71") (pintype "bidirectional"))
    )
    (net (code "88") (name "unconnected-(U$1-NC-PadP$48)") (class "Default")
      (node (ref "U$1") (pin "P$48") (pinfunction "NC_P$48") (pintype "bidirectional"))
    )
    (net (code "89") (name "unconnected-(U$1-NRST-PadP$6)") (class "Default")
      (node (ref "U$1") (pin "P$6") (pinfunction "NRST_P$6") (pintype "bidirectional"))
    )
    (net (code "90") (name "unconnected-(U$1-PA0-PadP$12)") (class "Default")
      (node (ref "U$1") (pin "P$12") (pinfunction "PA0_P$12") (pintype "bidirectional"))
    )
    (net (code "91") (name "unconnected-(U$1-PA1-PadP$11)") (class "Default")
      (node (ref "U$1") (pin "P$11") (pinfunction "PA1_P$11") (pintype "bidirectional"))
    )
    (net (code "92") (name "unconnected-(U$1-PA4-PadP$16)") (class "Default")
      (node (ref "U$1") (pin "P$16") (pinfunction "PA4_P$16") (pintype "bidirectional"))
    )
    (net (code "93") (name "unconnected-(U$1-PA5-PadP$15)") (class "Default")
      (node (ref "U$1") (pin "P$15") (pinfunction "PA5_P$15") (pintype "bidirectional"))
    )
    (net (code "94") (name "unconnected-(U$1-PA6-PadP$18)") (class "Default")
      (node (ref "U$1") (pin "P$18") (pinfunction "PA6_P$18") (pintype "bidirectional"))
    )
    (net (code "95") (name "unconnected-(U$1-PA7-PadP$17)") (class "Default")
      (node (ref "U$1") (pin "P$17") (pinfunction "PA7_P$17") (pintype "bidirectional"))
    )
    (net (code "96") (name "unconnected-(U$1-PA10-PadP$91)") (class "Default")
      (node (ref "U$1") (pin "P$91") (pinfunction "PA10_P$91") (pintype "bidirectional"))
    )
    (net (code "97") (name "unconnected-(U$1-PA13-PadP$92)") (class "Default")
      (node (ref "U$1") (pin "P$92") (pinfunction "PA13_P$92") (pintype "bidirectional"))
    )
    (net (code "98") (name "unconnected-(U$1-PA14-PadP$89)") (class "Default")
      (node (ref "U$1") (pin "P$89") (pinfunction "PA14_P$89") (pintype "bidirectional"))
    )
    (net (code "99") (name "unconnected-(U$1-PB0-PadP$22)") (class "Default")
      (node (ref "U$1") (pin "P$22") (pinfunction "PB0_P$22") (pintype "bidirectional"))
    )
    (net (code "100") (name "unconnected-(U$1-PB1-PadP$21)") (class "Default")
      (node (ref "U$1") (pin "P$21") (pinfunction "PB1_P$21") (pintype "bidirectional"))
    )
    (net (code "101") (name "unconnected-(U$1-PB2-PadP$24)") (class "Default")
      (node (ref "U$1") (pin "P$24") (pinfunction "PB2_P$24") (pintype "bidirectional"))
    )
    (net (code "102") (name "unconnected-(U$1-PB6-PadP$73)") (class "Default")
      (node (ref "U$1") (pin "P$73") (pinfunction "PB6_P$73") (pintype "bidirectional"))
    )
    (net (code "103") (name "unconnected-(U$1-PB7-PadP$74)") (class "Default")
      (node (ref "U$1") (pin "P$74") (pinfunction "PB7_P$74") (pintype "bidirectional"))
    )
    (net (code "104") (name "unconnected-(U$1-PB9-PadP$70)") (class "Default")
      (node (ref "U$1") (pin "P$70") (pinfunction "PB9_P$70") (pintype "bidirectional"))
    )
    (net (code "105") (name "unconnected-(U$1-PB10-PadP$34)") (class "Default")
      (node (ref "U$1") (pin "P$34") (pinfunction "PB10_P$34") (pintype "bidirectional"))
    )
    (net (code "106") (name "unconnected-(U$1-PB11-PadP$35)") (class "Default")
      (node (ref "U$1") (pin "P$35") (pinfunction "PB11_P$35") (pintype "bidirectional"))
    )
    (net (code "107") (name "unconnected-(U$1-PC0-PadP$8)") (class "Default")
      (node (ref "U$1") (pin "P$8") (pinfunction "PC0_P$8") (pintype "bidirectional"))
    )
    (net (code "108") (name "unconnected-(U$1-PC1-PadP$7)") (class "Default")
      (node (ref "U$1") (pin "P$7") (pinfunction "PC1_P$7") (pintype "bidirectional"))
    )
    (net (code "109") (name "unconnected-(U$1-PC2-PadP$10)") (class "Default")
      (node (ref "U$1") (pin "P$10") (pinfunction "PC2_P$10") (pintype "bidirectional"))
    )
    (net (code "110") (name "unconnected-(U$1-PC3-PadP$9)") (class "Default")
      (node (ref "U$1") (pin "P$9") (pinfunction "PC3_P$9") (pintype "bidirectional"))
    )
    (net (code "111") (name "unconnected-(U$1-PC4-PadP$20)") (class "Default")
      (node (ref "U$1") (pin "P$20") (pinfunction "PC4_P$20") (pintype "bidirectional"))
    )
    (net (code "112") (name "unconnected-(U$1-PC5-PadP$19)") (class "Default")
      (node (ref "U$1") (pin "P$19") (pinfunction "PC5_P$19") (pintype "bidirectional"))
    )
    (net (code "113") (name "unconnected-(U$1-PC6-PadP$97)") (class "Default")
      (node (ref "U$1") (pin "P$97") (pinfunction "PC6_P$97") (pintype "bidirectional"))
    )
    (net (code "114") (name "unconnected-(U$1-PC7-PadP$98)") (class "Default")
      (node (ref "U$1") (pin "P$98") (pinfunction "PC7_P$98") (pintype "bidirectional"))
    )
    (net (code "115") (name "unconnected-(U$1-PC9-PadP$96)") (class "Default")
      (node (ref "U$1") (pin "P$96") (pinfunction "PC9_P$96") (pintype "bidirectional"))
    )
    (net (code "116") (name "unconnected-(U$1-PC10-PadP$87)") (class "Default")
      (node (ref "U$1") (pin "P$87") (pinfunction "PC10_P$87") (pintype "bidirectional"))
    )
    (net (code "117") (name "unconnected-(U$1-PC12-PadP$85)") (class "Default")
      (node (ref "U$1") (pin "P$85") (pinfunction "PC12_P$85") (pintype "bidirectional"))
    )
    (net (code "118") (name "unconnected-(U$1-PC15-PadP$60)") (class "Default")
      (node (ref "U$1") (pin "P$60") (pinfunction "PC15_P$60") (pintype "bidirectional"))
    )
    (net (code "119") (name "unconnected-(U$1-PD0-PadP$86)") (class "Default")
      (node (ref "U$1") (pin "P$86") (pinfunction "PD0_P$86") (pintype "bidirectional"))
    )
    (net (code "120") (name "unconnected-(U$1-PD1-PadP$83)") (class "Default")
      (node (ref "U$1") (pin "P$83") (pinfunction "PD1_P$83") (pintype "bidirectional"))
    )
    (net (code "121") (name "unconnected-(U$1-PD2-PadP$84)") (class "Default")
      (node (ref "U$1") (pin "P$84") (pinfunction "PD2_P$84") (pintype "bidirectional"))
    )
    (net (code "122") (name "unconnected-(U$1-PD4-PadP$82)") (class "Default")
      (node (ref "U$1") (pin "P$82") (pinfunction "PD4_P$82") (pintype "bidirectional"))
    )
    (net (code "123") (name "unconnected-(U$1-PD5-PadP$79)") (class "Default")
      (node (ref "U$1") (pin "P$79") (pinfunction "PD5_P$79") (pintype "bidirectional"))
    )
    (net (code "124") (name "unconnected-(U$1-PD11-PadP$43)") (class "Default")
      (node (ref "U$1") (pin "P$43") (pinfunction "PD11_P$43") (pintype "bidirectional"))
    )
    (net (code "125") (name "unconnected-(U$1-PD12-PadP$44)") (class "Default")
      (node (ref "U$1") (pin "P$44") (pinfunction "PD12_P$44") (pintype "bidirectional"))
    )
    (net (code "126") (name "unconnected-(U$1-PD13-PadP$45)") (class "Default")
      (node (ref "U$1") (pin "P$45") (pinfunction "PD13_P$45") (pintype "bidirectional"))
    )
    (net (code "127") (name "unconnected-(U$1-PD14-PadP$46)") (class "Default")
      (node (ref "U$1") (pin "P$46") (pinfunction "PD14_P$46") (pintype "bidirectional"))
    )
    (net (code "128") (name "unconnected-(U$1-PD15-PadP$47)") (class "Default")
      (node (ref "U$1") (pin "P$47") (pinfunction "PD15_P$47") (pintype "bidirectional"))
    )
    (net (code "129") (name "unconnected-(U$1-PE0-PadP$67)") (class "Default")
      (node (ref "U$1") (pin "P$67") (pinfunction "PE0_P$67") (pintype "bidirectional"))
    )
    (net (code "130") (name "unconnected-(U$1-PE1-PadP$68)") (class "Default")
      (node (ref "U$1") (pin "P$68") (pinfunction "PE1_P$68") (pintype "bidirectional"))
    )
    (net (code "131") (name "unconnected-(U$1-PE2-PadP$65)") (class "Default")
      (node (ref "U$1") (pin "P$65") (pinfunction "PE2_P$65") (pintype "bidirectional"))
    )
    (net (code "132") (name "unconnected-(U$1-PE3-PadP$66)") (class "Default")
      (node (ref "U$1") (pin "P$66") (pinfunction "PE3_P$66") (pintype "bidirectional"))
    )
    (net (code "133") (name "unconnected-(U$1-PE6-PadP$61)") (class "Default")
      (node (ref "U$1") (pin "P$61") (pinfunction "PE6_P$61") (pintype "bidirectional"))
    )
    (net (code "134") (name "unconnected-(U$1-PE7-PadP$25)") (class "Default")
      (node (ref "U$1") (pin "P$25") (pinfunction "PE7_P$25") (pintype "bidirectional"))
    )
    (net (code "135") (name "unconnected-(U$1-PH0-PadP$57)") (class "Default")
      (node (ref "U$1") (pin "P$57") (pinfunction "PH0_P$57") (pintype "bidirectional"))
    )
    (net (code "136") (name "unconnected-(U$1-PH1-PadP$58)") (class "Default")
      (node (ref "U$1") (pin "P$58") (pinfunction "PH1_P$58") (pintype "bidirectional"))
    )
  )
)
